# LCD.net
KiCad netlist of a schematic drawn in EAGLE
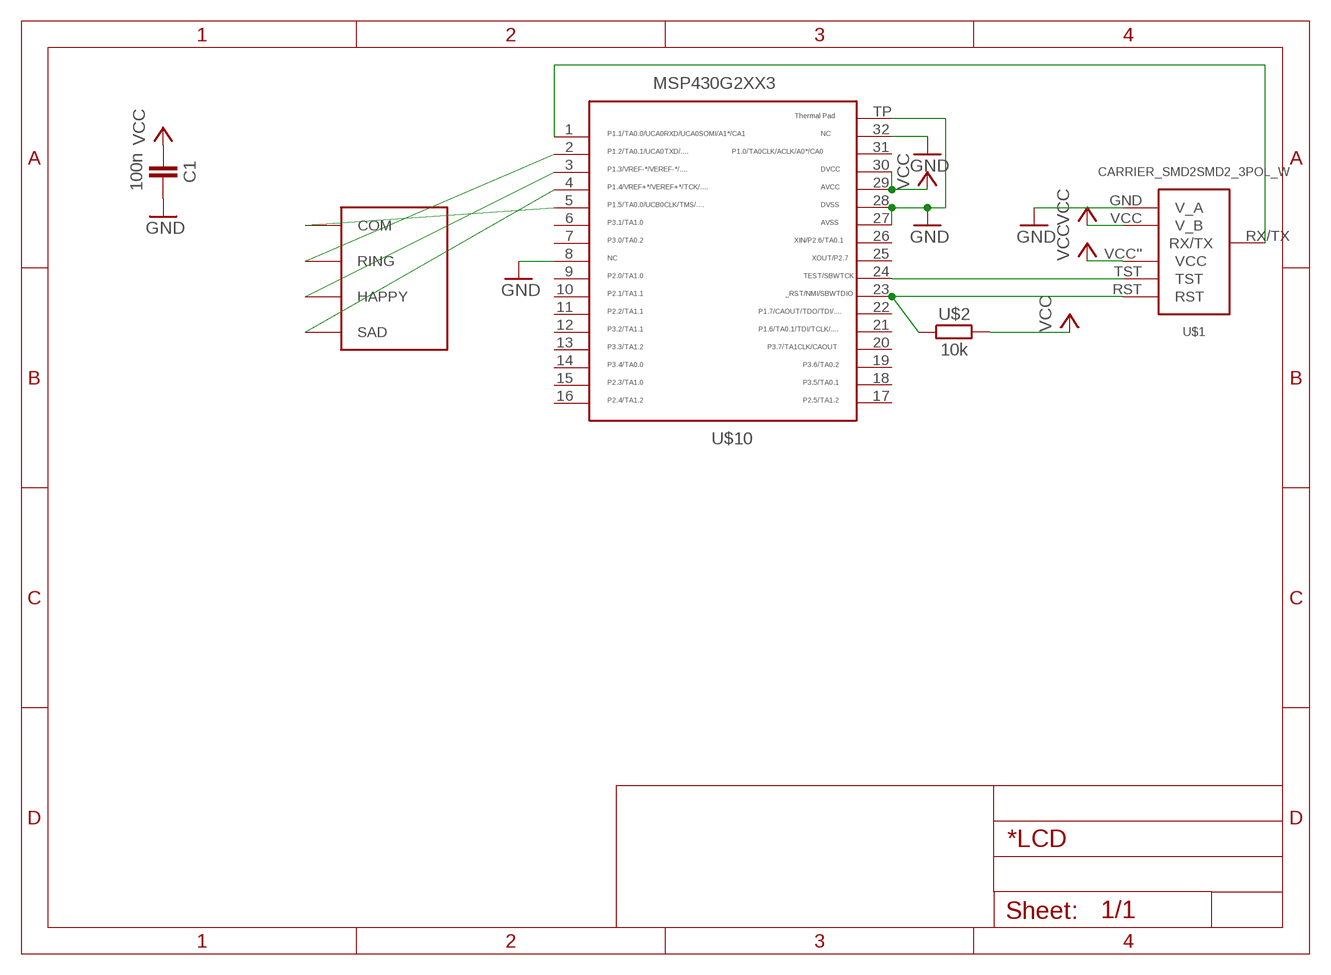
[diagram p0: schematic, sheet 1]

(export (version "E")
  (design (tool "Eeschema 10.0.6"))
  (components
    (comp (ref "C1")
      (value "100n")
      (footprint "eagle-import:603")
      (libsource (lib "eagle-import") (part "CAPACITOR"))
    )
    (comp (ref "U$1")
      (value "CARRIER_SMD2SMD2_3POL_W")
      (footprint "eagle-import:CARRIER_SMD2_WIDE_3POL")
      (libsource (lib "eagle-import") (part "CARRIER_SMD2SMD2_3POL_W"))
    )
    (comp (ref "U$2")
      (value "10k")
      (footprint "eagle-import:603")
      (libsource (lib "eagle-import") (part "RESISTOR0603"))
    )
    (comp (ref "U$3")
      (value "SMILEY")
      (footprint "eagle-import:SMILEY")
      (libsource (lib "eagle-import") (part "SMILEY"))
    )
    (comp (ref "U$10")
      (value "MSP430G2553")
      (footprint "eagle-import:QFN32")
      (libsource (lib "eagle-import") (part "MSP430G2553"))
    )
  )
  (nets
    (net (code "1") (name "GND") (class "Default")
      (node (ref "C1") (pin "2") (pinfunction "2_2") (pintype "passive"))
      (node (ref "U$1") (pin "GND") (pinfunction "V_A_GND") (pintype "bidirectional"))
      (node (ref "U$10") (pin "27") (pinfunction "27_27") (pintype "bidirectional"))
      (node (ref "U$10") (pin "28") (pinfunction "28_28") (pintype "bidirectional"))
      (node (ref "U$10") (pin "32") (pinfunction "32_32") (pintype "bidirectional"))
      (node (ref "U$10") (pin "8") (pinfunction "8_8") (pintype "bidirectional"))
      (node (ref "U$10") (pin "TP") (pinfunction "TP_TP") (pintype "bidirectional"))
    )
    (net (code "2") (name "Net-(U$1-PadRST)") (class "Default")
      (node (ref "U$1") (pin "RST") (pinfunction "RST_RST") (pintype "bidirectional"))
      (node (ref "U$10") (pin "23") (pinfunction "23_23") (pintype "bidirectional"))
      (node (ref "U$2") (pin "1") (pinfunction "1_1") (pintype "passive"))
    )
    (net (code "3") (name "Net-(U$1-PadRX{slash}TX)") (class "Default")
      (node (ref "U$1") (pin "RX/TX") (pinfunction "RX/TX_RX/TX") (pintype "bidirectional"))
      (node (ref "U$10") (pin "1") (pinfunction "1_1") (pintype "bidirectional"))
    )
    (net (code "4") (name "Net-(U$1-PadTST)") (class "Default")
      (node (ref "U$1") (pin "TST") (pinfunction "TST_TST") (pintype "bidirectional"))
      (node (ref "U$10") (pin "24") (pinfunction "24_24") (pintype "bidirectional"))
    )
    (net (code "5") (name "Net-(U$3-COM)") (class "Default")
      (node (ref "U$10") (pin "5") (pinfunction "5_5") (pintype "bidirectional"))
      (node (ref "U$3") (pin "1") (pinfunction "COM_1") (pintype "passive"))
    )
    (net (code "6") (name "Net-(U$3-HAPPY)") (class "Default")
      (node (ref "U$10") (pin "3") (pinfunction "3_3") (pintype "bidirectional"))
      (node (ref "U$3") (pin "3") (pinfunction "HAPPY_3") (pintype "passive"))
    )
    (net (code "7") (name "Net-(U$3-RING)") (class "Default")
      (node (ref "U$10") (pin "2") (pinfunction "2_2") (pintype "bidirectional"))
      (node (ref "U$3") (pin "4") (pinfunction "RING_4") (pintype "passive"))
    )
    (net (code "8") (name "Net-(U$3-SAD)") (class "Default")
      (node (ref "U$10") (pin "4") (pinfunction "4_4") (pintype "bidirectional"))
      (node (ref "U$3") (pin "2") (pinfunction "SAD_2") (pintype "passive"))
    )
    (net (code "9") (name "VCC") (class "Default")
      (node (ref "C1") (pin "1") (pinfunction "1_1") (pintype "passive"))
      (node (ref "U$1") (pin "VCC") (pinfunction "V_B_VCC") (pintype "bidirectional"))
      (node (ref "U$1") (pin "VCC''") (pinfunction "VCC_VCC''") (pintype "bidirectional"))
      (node (ref "U$10") (pin "29") (pinfunction "29_29") (pintype "bidirectional"))
      (node (ref "U$10") (pin "30") (pinfunction "30_30") (pintype "bidirectional"))
      (node (ref "U$2") (pin "2") (pinfunction "2_2") (pintype "passive"))
    )
    (net (code "10") (name "unconnected-(U$10-Pad6)") (class "Default")
      (node (ref "U$10") (pin "6") (pinfunction "6_6") (pintype "bidirectional"))
    )
    (net (code "11") (name "unconnected-(U$10-Pad7)") (class "Default")
      (node (ref "U$10") (pin "7") (pinfunction "7_7") (pintype "bidirectional"))
    )
    (net (code "12") (name "unconnected-(U$10-Pad9)") (class "Default")
      (node (ref "U$10") (pin "9") (pinfunction "9_9") (pintype "bidirectional"))
    )
    (net (code "13") (name "unconnected-(U$10-Pad10)") (class "Default")
      (node (ref "U$10") (pin "10") (pinfunction "10_10") (pintype "bidirectional"))
    )
    (net (code "14") (name "unconnected-(U$10-Pad11)") (class "Default")
      (node (ref "U$10") (pin "11") (pinfunction "11_11") (pintype "bidirectional"))
    )
    (net (code "15") (name "unconnected-(U$10-Pad12)") (class "Default")
      (node (ref "U$10") (pin "12") (pinfunction "12_12") (pintype "bidirectional"))
    )
    (net (code "16") (name "unconnected-(U$10-Pad13)") (class "Default")
      (node (ref "U$10") (pin "13") (pinfunction "13_13") (pintype "bidirectional"))
    )
    (net (code "17") (name "unconnected-(U$10-Pad14)") (class "Default")
      (node (ref "U$10") (pin "14") (pinfunction "14_14") (pintype "bidirectional"))
    )
    (net (code "18") (name "unconnected-(U$10-Pad15)") (class "Default")
      (node (ref "U$10") (pin "15") (pinfunction "15_15") (pintype "bidirectional"))
    )
    (net (code "19") (name "unconnected-(U$10-Pad16)") (class "Default")
      (node (ref "U$10") (pin "16") (pinfunction "16_16") (pintype "bidirectional"))
    )
    (net (code "20") (name "unconnected-(U$10-Pad17)") (class "Default")
      (node (ref "U$10") (pin "17") (pinfunction "17_17") (pintype "bidirectional"))
    )
    (net (code "21") (name "unconnected-(U$10-Pad18)") (class "Default")
      (node (ref "U$10") (pin "18") (pinfunction "18_18") (pintype "bidirectional"))
    )
    (net (code "22") (name "unconnected-(U$10-Pad19)") (class "Default")
      (node (ref "U$10") (pin "19") (pinfunction "19_19") (pintype "bidirectional"))
    )
    (net (code "23") (name "unconnected-(U$10-Pad20)") (class "Default")
      (node (ref "U$10") (pin "20") (pinfunction "20_20") (pintype "bidirectional"))
    )
    (net (code "24") (name "unconnected-(U$10-Pad21)") (class "Default")
      (node (ref "U$10") (pin "21") (pinfunction "21_21") (pintype "bidirectional"))
    )
    (net (code "25") (name "unconnected-(U$10-Pad22)") (class "Default")
      (node (ref "U$10") (pin "22") (pinfunction "22_22") (pintype "bidirectional"))
    )
    (net (code "26") (name "unconnected-(U$10-Pad25)") (class "Default")
      (node (ref "U$10") (pin "25") (pinfunction "25_25") (pintype "bidirectional"))
    )
    (net (code "27") (name "unconnected-(U$10-Pad26)") (class "Default")
      (node (ref "U$10") (pin "26") (pinfunction "26_26") (pintype "bidirectional"))
    )
    (net (code "28") (name "unconnected-(U$10-Pad31)") (class "Default")
      (node (ref "U$10") (pin "31") (pinfunction "31_31") (pintype "bidirectional"))
    )
  )
)
